# FIT_TCM_P1V8.net
KiCad netlist of a schematic drawn in Altium Designer
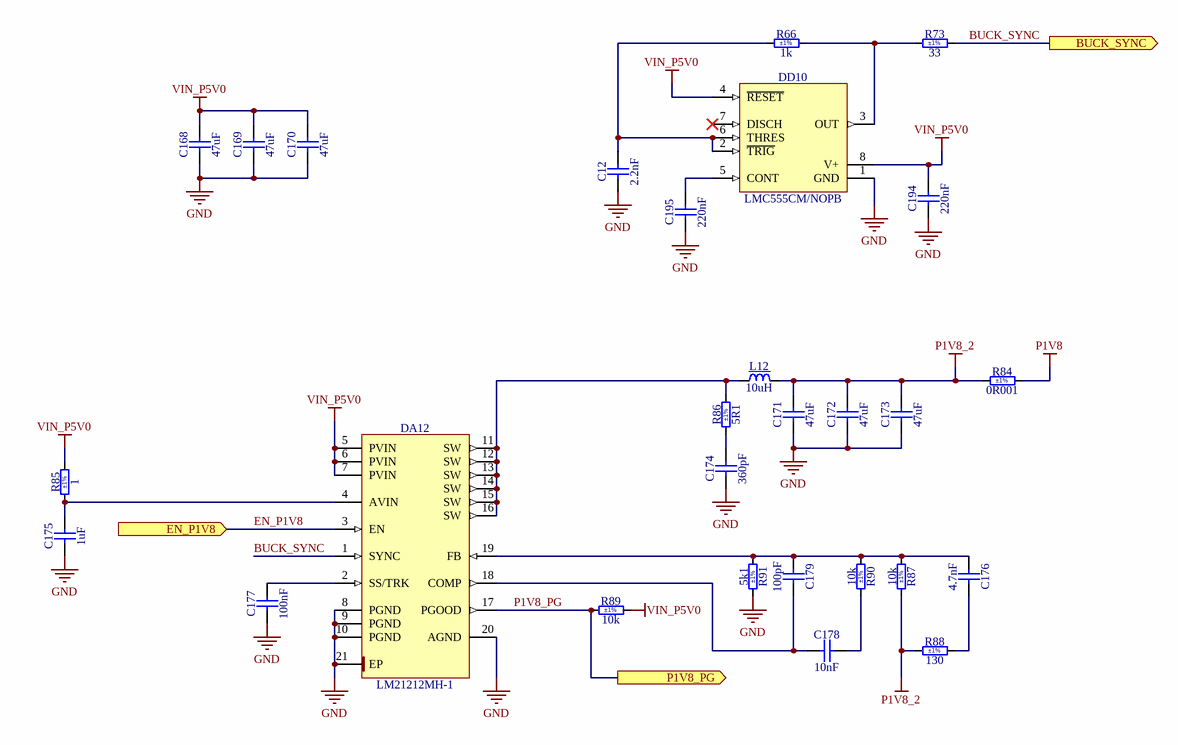
[diagram p0: FIT_TCM_P1V8.SchDoc]

(export (version "E")
  (design (tool "Eeschema 10.0.6"))
  (components
    (comp (ref "C12")
      (value "2.2nF")
      (footprint "CAPC2013X100N")
      (description "Non-polarised capacitor")
      (fields
        (field (name "PART NUMBER") "CC0805_2.2NF_50V_5%_C0G")
        (field (name "VOLTAGE") "50V")
        (field (name "AUTHOR") "CERN DEM MR")
      )
      (libsource (lib "Capacitors") (part "Capacitor - non polarized"))
    )
    (comp (ref "C168")
      (value "47uF")
      (footprint "CAPC3225X270N")
      (description "Non-polarised capacitor")
      (fields
        (field (name "PART NUMBER") "CC1210_47UF_16V_20%_X5R")
        (field (name "VOLTAGE") "16V")
        (field (name "AUTHOR") "CERN DEM MR")
      )
      (libsource (lib "Capacitors") (part "Capacitor - non polarized"))
    )
    (comp (ref "C169")
      (value "47uF")
      (footprint "CAPC3225X270N")
      (description "Non-polarised capacitor")
      (fields
        (field (name "PART NUMBER") "CC1210_47UF_16V_20%_X5R")
        (field (name "VOLTAGE") "16V")
        (field (name "AUTHOR") "CERN DEM MR")
      )
      (libsource (lib "Capacitors") (part "Capacitor - non polarized"))
    )
    (comp (ref "C170")
      (value "47uF")
      (footprint "CAPC3225X270N")
      (description "Non-polarised capacitor")
      (fields
        (field (name "PART NUMBER") "CC1210_47UF_16V_20%_X5R")
        (field (name "VOLTAGE") "16V")
        (field (name "AUTHOR") "CERN DEM MR")
      )
      (libsource (lib "Capacitors") (part "Capacitor - non polarized"))
    )
    (comp (ref "C171")
      (value "47uF")
      (footprint "CAPC3225X270N")
      (description "Non-polarised capacitor")
      (fields
        (field (name "PART NUMBER") "CC1210_47UF_16V_20%_X5R")
        (field (name "VOLTAGE") "16V")
        (field (name "AUTHOR") "CERN DEM MR")
      )
      (libsource (lib "Capacitors") (part "Capacitor - non polarized"))
    )
    (comp (ref "C172")
      (value "47uF")
      (footprint "CAPC3225X270N")
      (description "Non-polarised capacitor")
      (fields
        (field (name "PART NUMBER") "CC1210_47UF_16V_20%_X5R")
        (field (name "VOLTAGE") "16V")
        (field (name "AUTHOR") "CERN DEM MR")
      )
      (libsource (lib "Capacitors") (part "Capacitor - non polarized"))
    )
    (comp (ref "C173")
      (value "47uF")
      (footprint "CAPC3225X270N")
      (description "Non-polarised capacitor")
      (fields
        (field (name "PART NUMBER") "CC1210_47UF_16V_20%_X5R")
        (field (name "VOLTAGE") "16V")
        (field (name "AUTHOR") "CERN DEM MR")
      )
      (libsource (lib "Capacitors") (part "Capacitor - non polarized"))
    )
    (comp (ref "C174")
      (value "360pF")
      (footprint "CAPC2013X145N")
      (description "Non-polarised capacitor")
      (fields
        (field (name "PART NUMBER") "CC0805_360PF_50V_5%_C0G")
        (field (name "VOLTAGE") "50V")
        (field (name "AUTHOR") "CERN DEM HF")
      )
      (libsource (lib "Capacitors") (part "Capacitor - non polarized"))
    )
    (comp (ref "C175")
      (value "1uF")
      (footprint "CAPC2012X140N")
      (description "Non-polarised capacitor")
      (fields
        (field (name "PART NUMBER") "CC0805_1UF_25V_10%_X7R")
        (field (name "VOLTAGE") "25V")
        (field (name "AUTHOR") "CERN DEM JLC")
      )
      (libsource (lib "Capacitors") (part "Capacitor - non polarized"))
    )
    (comp (ref "C176")
      (value "4.7nF")
      (footprint "CAPC2012X95N")
      (description "Non-polarised capacitor")
      (fields
        (field (name "PART NUMBER") "CC0805_4.7NF_50V_5%_NP0")
        (field (name "VOLTAGE") "50V")
        (field (name "AUTHOR") "CERN DEM MR")
      )
      (libsource (lib "Capacitors") (part "Capacitor - non polarized"))
    )
    (comp (ref "C177")
      (value "100nF")
      (footprint "CAPC2012X135N")
      (description "Non-polarised capacitor")
      (fields
        (field (name "PART NUMBER") "CC0805_100NF_50V_10%_X7R")
        (field (name "VOLTAGE") "50V")
        (field (name "AUTHOR") "CERN DEM JLC")
      )
      (libsource (lib "Capacitors") (part "Capacitor - non polarized"))
    )
    (comp (ref "C178")
      (value "10nF")
      (footprint "CAPC2012X135N")
      (description "Non-polarised capacitor")
      (fields
        (field (name "PART NUMBER") "CC0805_10NF_50V_10%_X7R")
        (field (name "VOLTAGE") "50V")
        (field (name "AUTHOR") "CERN DEM JLC")
      )
      (libsource (lib "Capacitors") (part "Capacitor - non polarized"))
    )
    (comp (ref "C179")
      (value "100pF")
      (footprint "CAPC2012X135N")
      (description "Non-polarised capacitor")
      (fields
        (field (name "PART NUMBER") "CC0805_100PF_50V_5%_NP0")
        (field (name "VOLTAGE") "50V")
        (field (name "AUTHOR") "CERN DEM JLC")
      )
      (libsource (lib "Capacitors") (part "Capacitor - non polarized"))
    )
    (comp (ref "C194")
      (value "220nF")
      (footprint "CAPC2012X135N")
      (description "Non-polarised capacitor")
      (fields
        (field (name "PART NUMBER") "CC0805_220NF_50V_10%_X7R")
        (field (name "VOLTAGE") "50V")
        (field (name "AUTHOR") "CERN DEM JLC")
      )
      (libsource (lib "Capacitors") (part "Capacitor - non polarized"))
    )
    (comp (ref "C195")
      (value "220nF")
      (footprint "CAPC2012X135N")
      (description "Non-polarised capacitor")
      (fields
        (field (name "PART NUMBER") "CC0805_220NF_50V_10%_X7R")
        (field (name "VOLTAGE") "50V")
        (field (name "AUTHOR") "CERN DEM JLC")
      )
      (libsource (lib "Capacitors") (part "Capacitor - non polarized"))
    )
    (comp (ref "DA12")
      (value "LM21212MH-1")
      (footprint "TEXAS_PWP0020AA")
      (description "2.95-V To 5.5-V, 12-A, Voltage-Mode Synchronous Buck Regulator with Frequency Synchronization")
      (fields (field (name "MANUFACTURER") "TEXAS INSTRUMENTS") (field (name "AUTHOR") "CERN DEM HF"))
      (libsource (lib "ICs And Semiconductors") (part "LM21212"))
    )
    (comp (ref "DD10")
      (value "LMC555CM/NOPB")
      (footprint "SOIC127P600X175-8N")
      (description "CMOS Timer")
      (fields
        (field (name "MANUFACTURER") "NATIONAL SEMICONDUCTOR")
        (field (name "MANUFACTURER PART NUMBER") "LMC555CM")
        (field (name "AUTHOR") "CERN DEM JLC")
      )
      (libsource (lib "ICs And Semiconductors") (part "LMC555CM"))
    )
    (comp (ref "L12")
      (value "10uH")
      (footprint "IND_VISHAY_IHPL4040DZ-01")
      (description "Inductor With Core")
      (fields
        (field (name "PART NUMBER") "IND4040_10UH_20%_VISHAY_IHLP-4040DZ-01")
        (field (name "POWER") "6.8A")
        (field (name "AUTHOR") "CERN DEM HF")
      )
      (libsource (lib "Inductors & Transformers") (part "Inductor With Magnetic core"))
    )
    (comp (ref "R66")
      (value "1k")
      (footprint "RESC2012X60N")
      (description "Resistor - 1%")
      (fields
        (field (name "TOLERANCE") "±1%")
        (field (name "PART NUMBER") "R0805_1K_1%_0.125W_100PPM")
        (field (name "POWER") "0.125W")
        (field (name "AUTHOR") "CERN DEM JLC")
      )
      (libsource (lib "Resistors") (part "Resistor - 1%"))
    )
    (comp (ref "R73")
      (value "33")
      (footprint "RESC2012X60N")
      (description "Resistor - 1%")
      (fields
        (field (name "TOLERANCE") "±1%")
        (field (name "PART NUMBER") "R0805_33R_1%_0.125W_100PPM")
        (field (name "POWER") "0.125W")
        (field (name "AUTHOR") "CERN DEM JLC")
      )
      (libsource (lib "Resistors") (part "Resistor - 1%"))
    )
    (comp (ref "R84")
      (value "0R001")
      (footprint "RESC_BOURNS_CRE2512_0R001-0R004")
      (description "Resistor - 1%")
      (fields
        (field (name "TOLERANCE") "±1%")
        (field (name "PART NUMBER") "R2512_0R001_1%_3W_50PPM_BOURNS_CRE2512")
        (field (name "POWER") "3W")
        (field (name "AUTHOR") "CERN DEM BC")
      )
      (libsource (lib "Resistors") (part "Resistor - 1%"))
    )
    (comp (ref "R85")
      (value "1")
      (footprint "RESC2012X60N")
      (description "Resistor - 1%")
      (fields
        (field (name "TOLERANCE") "±1%")
        (field (name "PART NUMBER") "R0805_1R_1%_0.125W_100PPM")
        (field (name "POWER") "0.125W")
        (field (name "AUTHOR") "CERN DEM HF")
      )
      (libsource (lib "Resistors") (part "Resistor - 1%"))
    )
    (comp (ref "R86")
      (value "5R1")
      (footprint "RESC2012X60N")
      (description "Resistor - 1%")
      (fields
        (field (name "TOLERANCE") "±1%")
        (field (name "PART NUMBER") "R0805_5R1_1%_0.125W_100PPM")
        (field (name "POWER") "0.125W")
        (field (name "AUTHOR") "CERN DEM HF")
      )
      (libsource (lib "Resistors") (part "Resistor - 1%"))
    )
    (comp (ref "R87")
      (value "10k")
      (footprint "RESC2012X60N")
      (description "Resistor - 1%")
      (fields
        (field (name "TOLERANCE") "±1%")
        (field (name "PART NUMBER") "R0805_10K_1%_0.125W_100PPM")
        (field (name "POWER") "0.125W")
        (field (name "AUTHOR") "CERN DEM JLC")
      )
      (libsource (lib "Resistors") (part "Resistor - 1%"))
    )
    (comp (ref "R88")
      (value "130")
      (footprint "RESC2012X60N")
      (description "Resistor - 1%")
      (fields
        (field (name "TOLERANCE") "±1%")
        (field (name "PART NUMBER") "R0805_130R_1%_0.125W_100PPM")
        (field (name "POWER") "0.125W")
        (field (name "AUTHOR") "CERN DEM JLC")
      )
      (libsource (lib "Resistors") (part "Resistor - 1%"))
    )
    (comp (ref "R89")
      (value "10k")
      (footprint "RESC2012X60N")
      (description "Resistor - 1%")
      (fields
        (field (name "TOLERANCE") "±1%")
        (field (name "PART NUMBER") "R0805_10K_1%_0.125W_100PPM")
        (field (name "POWER") "0.125W")
        (field (name "AUTHOR") "CERN DEM JLC")
      )
      (libsource (lib "Resistors") (part "Resistor - 1%"))
    )
    (comp (ref "R90")
      (value "10k")
      (footprint "RESC2012X60N")
      (description "Resistor - 1%")
      (fields
        (field (name "TOLERANCE") "±1%")
        (field (name "PART NUMBER") "R0805_10K_1%_0.125W_100PPM")
        (field (name "POWER") "0.125W")
        (field (name "AUTHOR") "CERN DEM JLC")
      )
      (libsource (lib "Resistors") (part "Resistor - 1%"))
    )
    (comp (ref "R91")
      (value "5k1")
      (footprint "RESC2012X60N")
      (description "Resistor - 1%")
      (fields
        (field (name "TOLERANCE") "±1%")
        (field (name "PART NUMBER") "R0805_5K1_1%_0.125W_100PPM")
        (field (name "POWER") "0.125W")
        (field (name "AUTHOR") "CERN DEM JLC")
      )
      (libsource (lib "Resistors") (part "Resistor - 1%"))
    )
  )
  (nets
    (net (code "1") (name "/BUCK_SYNC") (class "Default")
      (node (ref "DA12") (pin "1") (pinfunction "SYNC_1") (pintype "input"))
      (node (ref "R73") (pin "2") (pinfunction "2_2") (pintype "passive"))
    )
    (net (code "2") (name "/EN_P1V8") (class "Default")
      (node (ref "DA12") (pin "3") (pinfunction "EN_3") (pintype "input"))
    )
    (net (code "3") (name "/P1V8_PG") (class "Default")
      (node (ref "DA12") (pin "17") (pinfunction "PGOOD_17") (pintype "output"))
      (node (ref "R89") (pin "1") (pinfunction "1_1") (pintype "passive"))
    )
    (net (code "4") (name "GND") (class "Default")
      (node (ref "C12") (pin "1") (pinfunction "1_1") (pintype "passive"))
      (node (ref "C168") (pin "1") (pinfunction "1_1") (pintype "passive"))
      (node (ref "C169") (pin "1") (pinfunction "1_1") (pintype "passive"))
      (node (ref "C170") (pin "1") (pinfunction "1_1") (pintype "passive"))
      (node (ref "C171") (pin "1") (pinfunction "1_1") (pintype "passive"))
      (node (ref "C172") (pin "1") (pinfunction "1_1") (pintype "passive"))
      (node (ref "C173") (pin "1") (pinfunction "1_1") (pintype "passive"))
      (node (ref "C174") (pin "1") (pinfunction "1_1") (pintype "passive"))
      (node (ref "C175") (pin "1") (pinfunction "1_1") (pintype "passive"))
      (node (ref "C177") (pin "1") (pinfunction "1_1") (pintype "passive"))
      (node (ref "C194") (pin "1") (pinfunction "1_1") (pintype "passive"))
      (node (ref "C195") (pin "1") (pinfunction "1_1") (pintype "passive"))
      (node (ref "DA12") (pin "10") (pinfunction "PGND_10") (pintype "power_in"))
      (node (ref "DA12") (pin "20") (pinfunction "AGND_20") (pintype "power_in"))
      (node (ref "DA12") (pin "21") (pinfunction "EP_21") (pintype "power_in"))
      (node (ref "DA12") (pin "8") (pinfunction "PGND_8") (pintype "power_in"))
      (node (ref "DA12") (pin "9") (pinfunction "PGND_9") (pintype "power_in"))
      (node (ref "DD10") (pin "1") (pinfunction "GND_1") (pintype "power_in"))
      (node (ref "R91") (pin "1") (pinfunction "1_1") (pintype "passive"))
    )
    (net (code "5") (name "Net-(C174-Pad2)") (class "Default")
      (node (ref "C174") (pin "2") (pinfunction "2_2") (pintype "passive"))
      (node (ref "R86") (pin "1") (pinfunction "1_1") (pintype "passive"))
    )
    (net (code "6") (name "Net-(C176-Pad1)") (class "Default")
      (node (ref "C176") (pin "1") (pinfunction "1_1") (pintype "passive"))
      (node (ref "R88") (pin "1") (pinfunction "1_1") (pintype "passive"))
    )
    (net (code "7") (name "Net-(C178-Pad1)") (class "Default")
      (node (ref "C178") (pin "1") (pinfunction "1_1") (pintype "passive"))
      (node (ref "R90") (pin "1") (pinfunction "1_1") (pintype "passive"))
    )
    (net (code "8") (name "Net-(DA12-AVIN)") (class "Default")
      (node (ref "C175") (pin "2") (pinfunction "2_2") (pintype "passive"))
      (node (ref "DA12") (pin "4") (pinfunction "AVIN_4") (pintype "power_in"))
      (node (ref "R85") (pin "1") (pinfunction "1_1") (pintype "passive"))
    )
    (net (code "9") (name "Net-(DA12-COMP)") (class "Default")
      (node (ref "C178") (pin "2") (pinfunction "2_2") (pintype "passive"))
      (node (ref "C179") (pin "1") (pinfunction "1_1") (pintype "passive"))
      (node (ref "DA12") (pin "18") (pinfunction "COMP_18") (pintype "output"))
    )
    (net (code "10") (name "Net-(DA12-FB)") (class "Default")
      (node (ref "C176") (pin "2") (pinfunction "2_2") (pintype "passive"))
      (node (ref "C179") (pin "2") (pinfunction "2_2") (pintype "passive"))
      (node (ref "DA12") (pin "19") (pinfunction "FB_19") (pintype "input"))
      (node (ref "R87") (pin "2") (pinfunction "2_2") (pintype "passive"))
      (node (ref "R90") (pin "2") (pinfunction "2_2") (pintype "passive"))
      (node (ref "R91") (pin "2") (pinfunction "2_2") (pintype "passive"))
    )
    (net (code "11") (name "Net-(DA12-SS{slash}TRK)") (class "Default")
      (node (ref "C177") (pin "2") (pinfunction "2_2") (pintype "passive"))
      (node (ref "DA12") (pin "2") (pinfunction "SS/TRK_2") (pintype "input"))
    )
    (net (code "12") (name "Net-(DA12-SW-Pad11)") (class "Default")
      (node (ref "DA12") (pin "11") (pinfunction "SW_11") (pintype "output"))
      (node (ref "DA12") (pin "12") (pinfunction "SW_12") (pintype "output"))
      (node (ref "DA12") (pin "13") (pinfunction "SW_13") (pintype "output"))
      (node (ref "DA12") (pin "14") (pinfunction "SW_14") (pintype "output"))
      (node (ref "DA12") (pin "15") (pinfunction "SW_15") (pintype "output"))
      (node (ref "DA12") (pin "16") (pinfunction "SW_16") (pintype "output"))
      (node (ref "L12") (pin "1") (pinfunction "1_1") (pintype "passive"))
      (node (ref "R86") (pin "2") (pinfunction "2_2") (pintype "passive"))
    )
    (net (code "13") (name "Net-(DD10-CONT)") (class "Default")
      (node (ref "C195") (pin "2") (pinfunction "2_2") (pintype "passive"))
      (node (ref "DD10") (pin "5") (pinfunction "CONT_5") (pintype "input"))
    )
    (net (code "14") (name "Net-(DD10-OUT)") (class "Default")
      (node (ref "DD10") (pin "3") (pinfunction "OUT_3") (pintype "output"))
      (node (ref "R66") (pin "2") (pinfunction "2_2") (pintype "passive"))
      (node (ref "R73") (pin "1") (pinfunction "1_1") (pintype "passive"))
    )
    (net (code "15") (name "Net-(DD10-THRES)") (class "Default")
      (node (ref "C12") (pin "2") (pinfunction "2_2") (pintype "passive"))
      (node (ref "DD10") (pin "2") (pinfunction "~{TRIG}_2") (pintype "input"))
      (node (ref "DD10") (pin "6") (pinfunction "THRES_6") (pintype "input"))
      (node (ref "R66") (pin "1") (pinfunction "1_1") (pintype "passive"))
    )
    (net (code "16") (name "P1V8") (class "Default")
      (node (ref "R84") (pin "2") (pinfunction "2_2") (pintype "passive"))
    )
    (net (code "17") (name "P1V8_2") (class "Default")
      (node (ref "C171") (pin "2") (pinfunction "2_2") (pintype "passive"))
      (node (ref "C172") (pin "2") (pinfunction "2_2") (pintype "passive"))
      (node (ref "C173") (pin "2") (pinfunction "2_2") (pintype "passive"))
      (node (ref "L12") (pin "2") (pinfunction "2_2") (pintype "passive"))
      (node (ref "R84") (pin "1") (pinfunction "1_1") (pintype "passive"))
      (node (ref "R87") (pin "1") (pinfunction "1_1") (pintype "passive"))
      (node (ref "R88") (pin "2") (pinfunction "2_2") (pintype "passive"))
    )
    (net (code "18") (name "VIN_P5V0") (class "Default")
      (node (ref "C168") (pin "2") (pinfunction "2_2") (pintype "passive"))
      (node (ref "C169") (pin "2") (pinfunction "2_2") (pintype "passive"))
      (node (ref "C170") (pin "2") (pinfunction "2_2") (pintype "passive"))
      (node (ref "C194") (pin "2") (pinfunction "2_2") (pintype "passive"))
      (node (ref "DA12") (pin "5") (pinfunction "PVIN_5") (pintype "power_in"))
      (node (ref "DA12") (pin "6") (pinfunction "PVIN_6") (pintype "power_in"))
      (node (ref "DA12") (pin "7") (pinfunction "PVIN_7") (pintype "power_in"))
      (node (ref "DD10") (pin "4") (pinfunction "~{RESET}_4") (pintype "input"))
      (node (ref "DD10") (pin "8") (pinfunction "V+_8") (pintype "power_in"))
      (node (ref "R85") (pin "2") (pinfunction "2_2") (pintype "passive"))
      (node (ref "R89") (pin "2") (pinfunction "2_2") (pintype "passive"))
    )
    (net (code "19") (name "unconnected-(DD10-DISCH-Pad7)") (class "Default")
      (node (ref "DD10") (pin "7") (pinfunction "DISCH_7") (pintype "input+no_connect"))
    )
  )
)
